# USB.net
KiCad netlist of a schematic drawn in Altium Designer
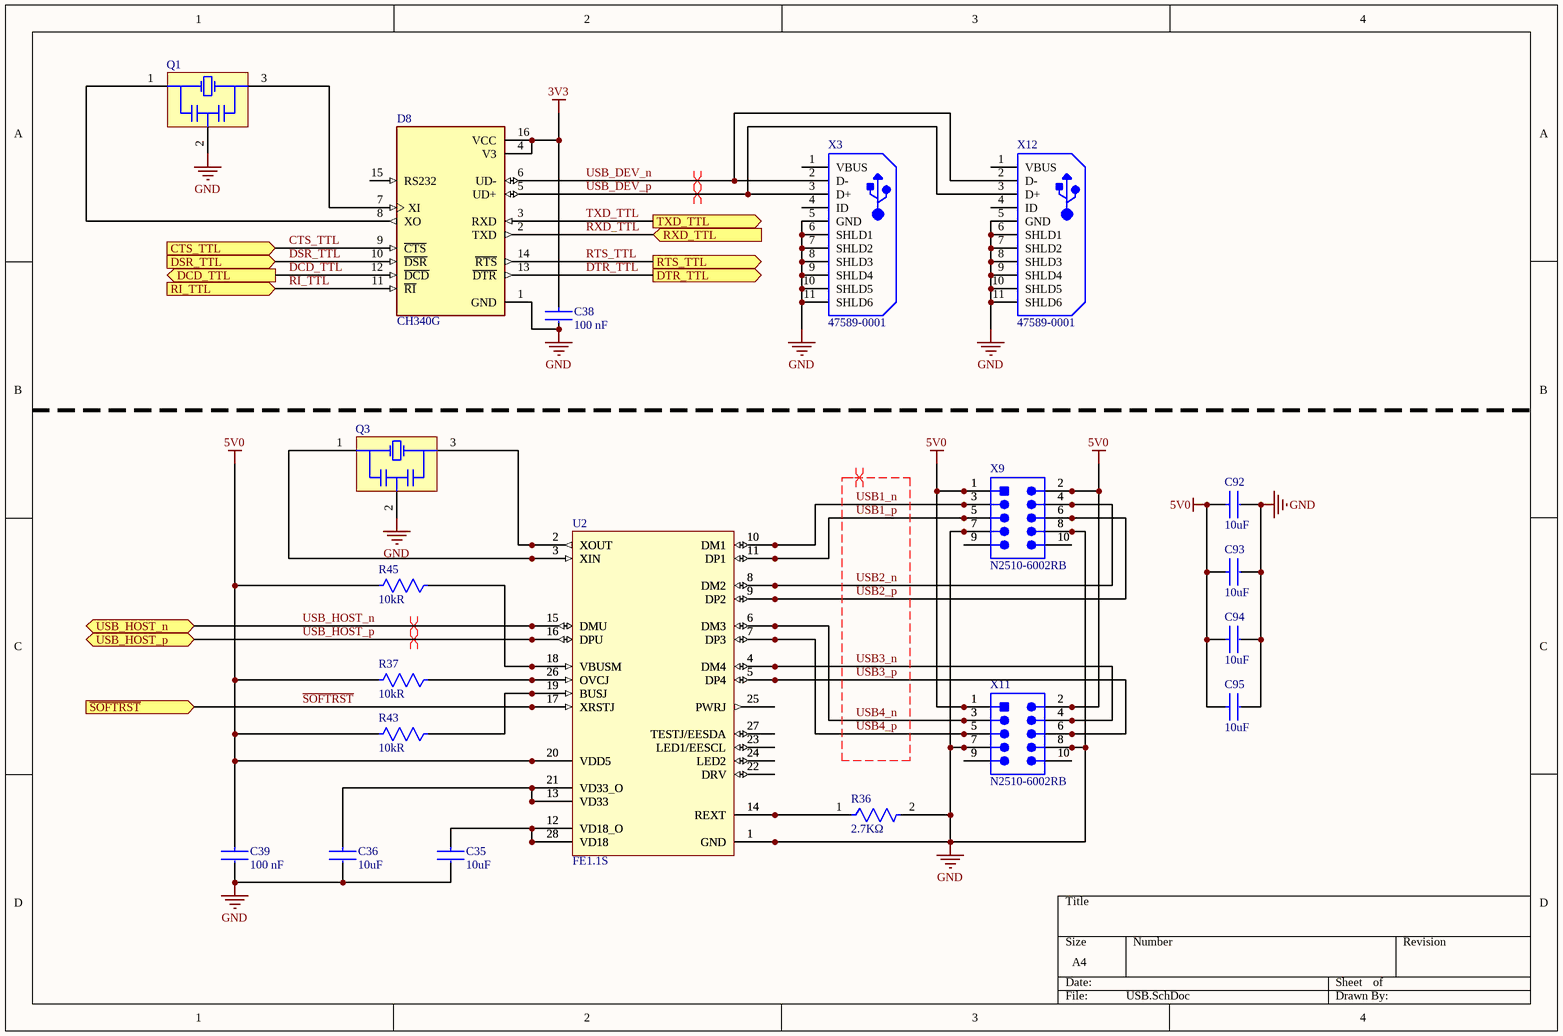
[diagram p0: USB.SchDoc]

(export (version "E")
  (design (tool "Eeschema 10.0.6"))
  (components
    (comp (ref "C35")
      (value "C0805C106K8PACTU")
      (footprint "FP-C0805C-DG-IPC_A")
      (description "CAP CER 10UF 10V X5R 0805")
      (fields (field (name "MANUFACTURER") "KEMET") (field (name "CAPACITANCE") "10uF"))
      (libsource (lib "SchLib") (part "CMP-2007-03243-2"))
    )
    (comp (ref "C36")
      (value "C0805C106K8PACTU")
      (footprint "FP-C0805C-DG-IPC_A")
      (description "CAP CER 10UF 10V X5R 0805")
      (fields (field (name "MANUFACTURER") "KEMET") (field (name "CAPACITANCE") "10uF"))
      (libsource (lib "SchLib") (part "CMP-2007-03243-2"))
    )
    (comp (ref "C38")
      (value "CC0805KRX7R9BB104")
      (footprint "FP-CC0805-0_85-IPC_A")
      (description "CAP CER 0.1UF 50V X7R 0805")
      (fields (field (name "MANUFACTURER") "Yageo") (field (name "CAPACITANCE") "100 nF"))
      (libsource (lib "SchLib") (part "CMP-2100-03606-3"))
    )
    (comp (ref "C39")
      (value "CC0805KRX7R9BB104")
      (footprint "FP-CC0805-0_85-IPC_A")
      (description "CAP CER 0.1UF 50V X7R 0805")
      (fields (field (name "MANUFACTURER") "Yageo") (field (name "CAPACITANCE") "100 nF"))
      (libsource (lib "SchLib") (part "CMP-2100-03606-3"))
    )
    (comp (ref "C92")
      (value "C0805C106K8PACTU")
      (footprint "FP-C0805C-DG-IPC_A")
      (description "CAP CER 10UF 10V X5R 0805")
      (fields (field (name "MANUFACTURER") "KEMET") (field (name "CAPACITANCE") "10uF"))
      (libsource (lib "SchLib") (part "CMP-2007-03243-2"))
    )
    (comp (ref "C93")
      (value "C0805C106K8PACTU")
      (footprint "FP-C0805C-DG-IPC_A")
      (description "CAP CER 10UF 10V X5R 0805")
      (fields (field (name "MANUFACTURER") "KEMET") (field (name "CAPACITANCE") "10uF"))
      (libsource (lib "SchLib") (part "CMP-2007-03243-2"))
    )
    (comp (ref "C94")
      (value "C0805C106K8PACTU")
      (footprint "FP-C0805C-DG-IPC_A")
      (description "CAP CER 10UF 10V X5R 0805")
      (fields (field (name "MANUFACTURER") "KEMET") (field (name "CAPACITANCE") "10uF"))
      (libsource (lib "SchLib") (part "CMP-2007-03243-2"))
    )
    (comp (ref "C95")
      (value "C0805C106K8PACTU")
      (footprint "FP-C0805C-DG-IPC_A")
      (description "CAP CER 10UF 10V X5R 0805")
      (fields (field (name "MANUFACTURER") "KEMET") (field (name "CAPACITANCE") "10uF"))
      (libsource (lib "SchLib") (part "CMP-2007-03243-2"))
    )
    (comp (ref "D8")
      (value "CH340G")
      (footprint "SOIC127P600X180-16N")
      (description "USB Interface Integrated Circuit")
      (libsource (lib "SchLib") (part "CH340G"))
    )
    (comp (ref "Q1")
      (value "CSTCE12M0G55Z-R0")
      (footprint "MURA-CSTCE_G_V")
      (description "Ceramic Resonator, 12 MHz, +/- 0.5%, -40 to 125 degC, 3-Pin SMD, RoHS, Tape and Reel")
      (fields (field (name "MANUFACTURER") "Murata"))
      (libsource (lib "SchLib") (part "CMP-2000-06123-1"))
    )
    (comp (ref "Q3")
      (value "CSTCE12M0G55Z-R0")
      (footprint "MURA-CSTCE_G_V")
      (description "Ceramic Resonator, 12 MHz, +/- 0.5%, -40 to 125 degC, 3-Pin SMD, RoHS, Tape and Reel")
      (fields (field (name "MANUFACTURER") "Murata"))
      (libsource (lib "SchLib") (part "CMP-2000-06123-1"))
    )
    (comp (ref "R36")
      (value "AC0805FR-072K7L")
      (footprint "FP-AC0805-IPC_A")
      (description "RES SMD 2.7K OHM 1% 1/8W 0805")
      (fields (field (name "RESISTANCE") "2.7KΩ") (field (name "MANUFACTURER") "Yageo"))
      (libsource (lib "SchLib") (part "CMP-2001-04496-2"))
    )
    (comp (ref "R37")
      (value "CR0805-JW-103ELF")
      (footprint "FP-CR0805-IPC_A")
      (description "Thick Film Chip Resistors 0805 10kΩ 0.125W 5% 200ppm/°C")
      (fields (field (name "RESISTANCE") "10kR") (field (name "MANUFACTURER") "Bourns"))
      (libsource (lib "SchLib") (part "CMP-07231-003873-1"))
    )
    (comp (ref "R43")
      (value "CR0805-JW-103ELF")
      (footprint "FP-CR0805-IPC_A")
      (description "Thick Film Chip Resistors 0805 10kΩ 0.125W 5% 200ppm/°C")
      (fields (field (name "RESISTANCE") "10kR") (field (name "MANUFACTURER") "Bourns"))
      (libsource (lib "SchLib") (part "CMP-07231-003873-1"))
    )
    (comp (ref "R45")
      (value "CR0805-JW-103ELF")
      (footprint "FP-CR0805-IPC_A")
      (description "Thick Film Chip Resistors 0805 10kΩ 0.125W 5% 200ppm/°C")
      (fields (field (name "RESISTANCE") "10kR") (field (name "MANUFACTURER") "Bourns"))
      (libsource (lib "SchLib") (part "CMP-07231-003873-1"))
    )
    (comp (ref "U2")
      (value "FE1.1S")
      (footprint "TSOP64P600X160-28L")
      (description "USB 2.0 HIGH SPEED 4-PORT HUB CONTROLLER")
      (fields (field (name "MANUFACTURER") "Terminus Technology Inc"))
      (libsource (lib "SchLib") (part "FE1.1S"))
    )
    (comp (ref "X3")
      (value "47589-0001")
      (footprint "MOLX-47589-0001_V")
      (description "Right Angle Female Type AB Micro USB Connector, 30 V, 1.8 A, -30 to 85 degC, RoHS, Tape and Reel")
      (fields (field (name "MANUFACTURER") "Molex"))
      (libsource (lib "SchLib") (part "CMP-2000-05610-1"))
    )
    (comp (ref "X9")
      (value "N2510-6002RB")
      (footprint "3M-N2510-6002-10_V")
      (fields (field (name "PARTNUMBER") "N2510") (field (name "MANUFACTURER") "3M"))
      (libsource (lib "SchLib") (part "CMP-2000-06794-1"))
    )
    (comp (ref "X11")
      (value "N2510-6002RB")
      (footprint "3M-N2510-6002-10_V")
      (fields (field (name "PARTNUMBER") "N2510") (field (name "MANUFACTURER") "3M"))
      (libsource (lib "SchLib") (part "CMP-2000-06794-1"))
    )
    (comp (ref "X12")
      (value "47589-0001")
      (footprint "MOLX-47589-0001_V")
      (description "Right Angle Female Type AB Micro USB Connector, 30 V, 1.8 A, -30 to 85 degC, RoHS, Tape and Reel")
      (fields (field (name "MANUFACTURER") "Molex"))
      (libsource (lib "SchLib") (part "CMP-2000-05610-1"))
    )
  )
  (nets
    (net (code "1") (name "/CTS_TTL") (class "Default")
      (node (ref "D8") (pin "9") (pinfunction "~{CTS}_9") (pintype "input"))
    )
    (net (code "2") (name "/DCD_TTL") (class "Default")
      (node (ref "D8") (pin "12") (pinfunction "~{DCD}_12") (pintype "input"))
    )
    (net (code "3") (name "/DSR_TTL") (class "Default")
      (node (ref "D8") (pin "10") (pinfunction "~{DSR}_10") (pintype "input"))
    )
    (net (code "4") (name "/DTR_TTL") (class "Default")
      (node (ref "D8") (pin "13") (pinfunction "~{DTR}_13") (pintype "output"))
    )
    (net (code "5") (name "/RI_TTL") (class "Default")
      (node (ref "D8") (pin "11") (pinfunction "~{RI}_11") (pintype "input"))
    )
    (net (code "6") (name "/RTS_TTL") (class "Default")
      (node (ref "D8") (pin "14") (pinfunction "~{RTS}_14") (pintype "output"))
    )
    (net (code "7") (name "/RXD_TTL") (class "Default")
      (node (ref "D8") (pin "2") (pinfunction "TXD_2") (pintype "output"))
    )
    (net (code "8") (name "/TXD_TTL") (class "Default")
      (node (ref "D8") (pin "3") (pinfunction "RXD_3") (pintype "input"))
    )
    (net (code "9") (name "/USB1_n") (class "Default")
      (node (ref "U2") (pin "10") (pinfunction "DM1_10") (pintype "bidirectional"))
      (node (ref "X9") (pin "3") (pinfunction "3_3") (pintype "passive"))
    )
    (net (code "10") (name "/USB1_p") (class "Default")
      (node (ref "U2") (pin "11") (pinfunction "DP1_11") (pintype "bidirectional"))
      (node (ref "X9") (pin "5") (pinfunction "5_5") (pintype "passive"))
    )
    (net (code "11") (name "/USB2_n") (class "Default")
      (node (ref "U2") (pin "8") (pinfunction "DM2_8") (pintype "bidirectional"))
      (node (ref "X9") (pin "4") (pinfunction "4_4") (pintype "passive"))
    )
    (net (code "12") (name "/USB2_p") (class "Default")
      (node (ref "U2") (pin "9") (pinfunction "DP2_9") (pintype "bidirectional"))
      (node (ref "X9") (pin "6") (pinfunction "6_6") (pintype "passive"))
    )
    (net (code "13") (name "/USB3_n") (class "Default")
      (node (ref "U2") (pin "4") (pinfunction "DM4_4") (pintype "bidirectional"))
      (node (ref "X11") (pin "4") (pinfunction "4_4") (pintype "passive"))
    )
    (net (code "14") (name "/USB3_p") (class "Default")
      (node (ref "U2") (pin "5") (pinfunction "DP4_5") (pintype "bidirectional"))
      (node (ref "X11") (pin "6") (pinfunction "6_6") (pintype "passive"))
    )
    (net (code "15") (name "/USB4_n") (class "Default")
      (node (ref "U2") (pin "6") (pinfunction "DM3_6") (pintype "bidirectional"))
      (node (ref "X11") (pin "3") (pinfunction "3_3") (pintype "passive"))
    )
    (net (code "16") (name "/USB4_p") (class "Default")
      (node (ref "U2") (pin "7") (pinfunction "DP3_7") (pintype "bidirectional"))
      (node (ref "X11") (pin "5") (pinfunction "5_5") (pintype "passive"))
    )
    (net (code "17") (name "/USB_DEV_n") (class "Default")
      (node (ref "D8") (pin "6") (pinfunction "UD-_6") (pintype "bidirectional"))
      (node (ref "X12") (pin "2") (pinfunction "D-_2") (pintype "passive"))
      (node (ref "X3") (pin "2") (pinfunction "D-_2") (pintype "passive"))
    )
    (net (code "18") (name "/USB_DEV_p") (class "Default")
      (node (ref "D8") (pin "5") (pinfunction "UD+_5") (pintype "bidirectional"))
      (node (ref "X12") (pin "3") (pinfunction "D+_3") (pintype "passive"))
      (node (ref "X3") (pin "3") (pinfunction "D+_3") (pintype "passive"))
    )
    (net (code "19") (name "/USB_HOST_n") (class "Default")
      (node (ref "U2") (pin "15") (pinfunction "DMU_15") (pintype "bidirectional"))
    )
    (net (code "20") (name "/USB_HOST_p") (class "Default")
      (node (ref "U2") (pin "16") (pinfunction "DPU_16") (pintype "bidirectional"))
    )
    (net (code "21") (name "/~{SOFTRST}") (class "Default")
      (node (ref "U2") (pin "17") (pinfunction "XRSTJ_17") (pintype "input"))
    )
    (net (code "22") (name "3V3") (class "Default")
      (node (ref "C38") (pin "1") (pinfunction "1_1") (pintype "passive"))
      (node (ref "D8") (pin "16") (pinfunction "VCC_16") (pintype "power_in"))
      (node (ref "D8") (pin "4") (pinfunction "V3_4") (pintype "power_in"))
    )
    (net (code "23") (name "5V0") (class "Default")
      (node (ref "C39") (pin "1") (pinfunction "1_1") (pintype "passive"))
      (node (ref "C92") (pin "1") (pinfunction "1_1") (pintype "passive"))
      (node (ref "C93") (pin "1") (pinfunction "1_1") (pintype "passive"))
      (node (ref "C94") (pin "1") (pinfunction "1_1") (pintype "passive"))
      (node (ref "C95") (pin "1") (pinfunction "1_1") (pintype "passive"))
      (node (ref "R37") (pin "2") (pinfunction "2_2") (pintype "passive"))
      (node (ref "R43") (pin "2") (pinfunction "2_2") (pintype "passive"))
      (node (ref "R45") (pin "2") (pinfunction "2_2") (pintype "passive"))
      (node (ref "U2") (pin "20") (pinfunction "VDD5_20") (pintype "power_in"))
      (node (ref "X11") (pin "1") (pinfunction "1_1") (pintype "passive"))
      (node (ref "X11") (pin "2") (pinfunction "2_2") (pintype "passive"))
      (node (ref "X9") (pin "1") (pinfunction "1_1") (pintype "passive"))
      (node (ref "X9") (pin "2") (pinfunction "2_2") (pintype "passive"))
    )
    (net (code "24") (name "GND") (class "Default")
      (node (ref "C35") (pin "2") (pinfunction "2_2") (pintype "passive"))
      (node (ref "C36") (pin "2") (pinfunction "2_2") (pintype "passive"))
      (node (ref "C38") (pin "2") (pinfunction "2_2") (pintype "passive"))
      (node (ref "C39") (pin "2") (pinfunction "2_2") (pintype "passive"))
      (node (ref "C92") (pin "2") (pinfunction "2_2") (pintype "passive"))
      (node (ref "C93") (pin "2") (pinfunction "2_2") (pintype "passive"))
      (node (ref "C94") (pin "2") (pinfunction "2_2") (pintype "passive"))
      (node (ref "C95") (pin "2") (pinfunction "2_2") (pintype "passive"))
      (node (ref "D8") (pin "1") (pinfunction "GND_1") (pintype "power_in"))
      (node (ref "Q1") (pin "2") (pinfunction "GND_2") (pintype "power_in"))
      (node (ref "Q3") (pin "2") (pinfunction "GND_2") (pintype "power_in"))
      (node (ref "R36") (pin "2") (pinfunction "2_2") (pintype "passive"))
      (node (ref "U2") (pin "1") (pinfunction "GND_1") (pintype "power_in"))
      (node (ref "X11") (pin "7") (pinfunction "7_7") (pintype "passive"))
      (node (ref "X11") (pin "8") (pinfunction "8_8") (pintype "passive"))
      (node (ref "X12") (pin "10") (pinfunction "SHLD5_10") (pintype "passive"))
      (node (ref "X12") (pin "11") (pinfunction "SHLD6_11") (pintype "passive"))
      (node (ref "X12") (pin "5") (pinfunction "GND_5") (pintype "passive"))
      (node (ref "X12") (pin "6") (pinfunction "SHLD1_6") (pintype "passive"))
      (node (ref "X12") (pin "7") (pinfunction "SHLD2_7") (pintype "passive"))
      (node (ref "X12") (pin "8") (pinfunction "SHLD3_8") (pintype "passive"))
      (node (ref "X12") (pin "9") (pinfunction "SHLD4_9") (pintype "passive"))
      (node (ref "X3") (pin "10") (pinfunction "SHLD5_10") (pintype "passive"))
      (node (ref "X3") (pin "11") (pinfunction "SHLD6_11") (pintype "passive"))
      (node (ref "X3") (pin "5") (pinfunction "GND_5") (pintype "passive"))
      (node (ref "X3") (pin "6") (pinfunction "SHLD1_6") (pintype "passive"))
      (node (ref "X3") (pin "7") (pinfunction "SHLD2_7") (pintype "passive"))
      (node (ref "X3") (pin "8") (pinfunction "SHLD3_8") (pintype "passive"))
      (node (ref "X3") (pin "9") (pinfunction "SHLD4_9") (pintype "passive"))
      (node (ref "X9") (pin "7") (pinfunction "7_7") (pintype "passive"))
      (node (ref "X9") (pin "8") (pinfunction "8_8") (pintype "passive"))
    )
    (net (code "25") (name "Net-(D8-XI)") (class "Default")
      (node (ref "D8") (pin "7") (pinfunction "XI_7") (pintype "input"))
      (node (ref "Q1") (pin "3") (pinfunction "X2_3") (pintype "passive"))
    )
    (net (code "26") (name "Net-(D8-XO)") (class "Default")
      (node (ref "D8") (pin "8") (pinfunction "XO_8") (pintype "output"))
      (node (ref "Q1") (pin "1") (pinfunction "X1_1") (pintype "passive"))
    )
    (net (code "27") (name "Net-(Q3-X1)") (class "Default")
      (node (ref "Q3") (pin "1") (pinfunction "X1_1") (pintype "passive"))
      (node (ref "U2") (pin "3") (pinfunction "XIN_3") (pintype "input"))
    )
    (net (code "28") (name "Net-(Q3-X2)") (class "Default")
      (node (ref "Q3") (pin "3") (pinfunction "X2_3") (pintype "passive"))
      (node (ref "U2") (pin "2") (pinfunction "XOUT_2") (pintype "output"))
    )
    (net (code "29") (name "Net-(U2-BUSJ)") (class "Default")
      (node (ref "R43") (pin "1") (pinfunction "1_1") (pintype "passive"))
      (node (ref "U2") (pin "19") (pinfunction "BUSJ_19") (pintype "input"))
    )
    (net (code "30") (name "Net-(U2-DRV)") (class "Default")
      (node (ref "U2") (pin "22") (pinfunction "DRV_22") (pintype "bidirectional"))
    )
    (net (code "31") (name "Net-(U2-LED1{slash}EESCL)") (class "Default")
      (node (ref "U2") (pin "23") (pinfunction "LED1/EESCL_23") (pintype "bidirectional"))
    )
    (net (code "32") (name "Net-(U2-LED2)") (class "Default")
      (node (ref "U2") (pin "24") (pinfunction "LED2_24") (pintype "bidirectional"))
    )
    (net (code "33") (name "Net-(U2-OVCJ)") (class "Default")
      (node (ref "R37") (pin "1") (pinfunction "1_1") (pintype "passive"))
      (node (ref "U2") (pin "26") (pinfunction "OVCJ_26") (pintype "input"))
    )
    (net (code "34") (name "Net-(U2-PWRJ)") (class "Default")
      (node (ref "U2") (pin "25") (pinfunction "PWRJ_25") (pintype "output"))
    )
    (net (code "35") (name "Net-(U2-REXT)") (class "Default")
      (node (ref "R36") (pin "1") (pinfunction "1_1") (pintype "passive"))
      (node (ref "U2") (pin "14") (pinfunction "REXT_14") (pintype "power_in"))
    )
    (net (code "36") (name "Net-(U2-TESTJ{slash}EESDA)") (class "Default")
      (node (ref "U2") (pin "27") (pinfunction "TESTJ/EESDA_27") (pintype "bidirectional"))
    )
    (net (code "37") (name "Net-(U2-VBUSM)") (class "Default")
      (node (ref "R45") (pin "1") (pinfunction "1_1") (pintype "passive"))
      (node (ref "U2") (pin "18") (pinfunction "VBUSM_18") (pintype "input"))
    )
    (net (code "38") (name "Net-(U2-VD18)") (class "Default")
      (node (ref "C35") (pin "1") (pinfunction "1_1") (pintype "passive"))
      (node (ref "U2") (pin "12") (pinfunction "VD18_O_12") (pintype "power_in"))
      (node (ref "U2") (pin "28") (pinfunction "VD18_28") (pintype "power_in"))
    )
    (net (code "39") (name "Net-(U2-VD33)") (class "Default")
      (node (ref "C36") (pin "1") (pinfunction "1_1") (pintype "passive"))
      (node (ref "U2") (pin "13") (pinfunction "VD33_13") (pintype "power_in"))
      (node (ref "U2") (pin "21") (pinfunction "VD33_O_21") (pintype "power_in"))
    )
    (net (code "40") (name "Net-(X9-Pad9)") (class "Default")
      (node (ref "X9") (pin "9") (pinfunction "9_9") (pintype "passive"))
    )
    (net (code "41") (name "Net-(X9-Pad10)") (class "Default")
      (node (ref "X9") (pin "10") (pinfunction "10_10") (pintype "passive"))
    )
    (net (code "42") (name "Net-(X11-Pad9)") (class "Default")
      (node (ref "X11") (pin "9") (pinfunction "9_9") (pintype "passive"))
    )
    (net (code "43") (name "Net-(X11-Pad10)") (class "Default")
      (node (ref "X11") (pin "10") (pinfunction "10_10") (pintype "passive"))
    )
    (net (code "44") (name "unconnected-(D8-RS232-Pad15)") (class "Default")
      (node (ref "D8") (pin "15") (pinfunction "RS232_15") (pintype "input"))
    )
    (net (code "45") (name "unconnected-(X3-ID-Pad4)") (class "Default")
      (node (ref "X3") (pin "4") (pinfunction "ID_4") (pintype "passive"))
    )
    (net (code "46") (name "unconnected-(X3-VBUS-Pad1)") (class "Default")
      (node (ref "X3") (pin "1") (pinfunction "VBUS_1") (pintype "passive"))
    )
    (net (code "47") (name "unconnected-(X12-ID-Pad4)") (class "Default")
      (node (ref "X12") (pin "4") (pinfunction "ID_4") (pintype "passive"))
    )
    (net (code "48") (name "unconnected-(X12-VBUS-Pad1)") (class "Default")
      (node (ref "X12") (pin "1") (pinfunction "VBUS_1") (pintype "passive"))
    )
  )
)
